# processor_main_connector.net
KiCad netlist of a schematic drawn in Altium Designer
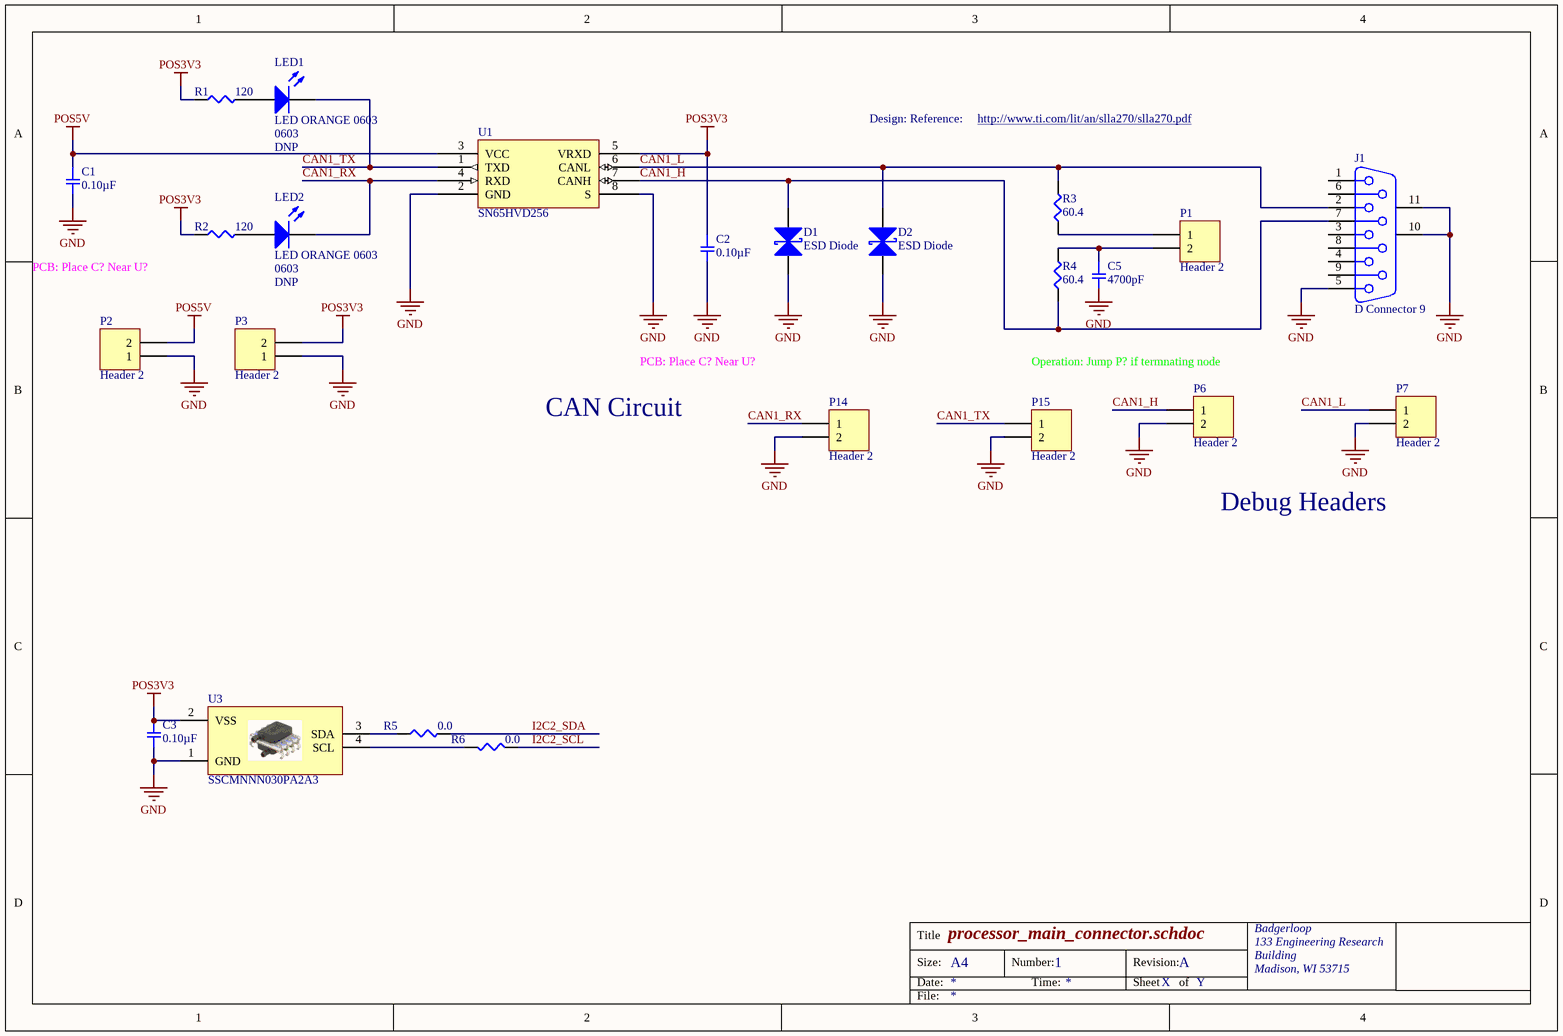
[diagram p0: processor_main_connector.SchDoc]

(export (version "E")
  (design (tool "Eeschema 10.0.6"))
  (components
    (comp (ref "C1")
      (value "0.10µF")
      (footprint "SMD-0805C")
      (description "CAP CER 0.1UF 50V X7R 0805")
      (fields
        (field (name "DIGI-KEY PART NUMBER") "490-11955-1-ND")
        (field (name "PART NUMBER") "GCD21BR71H104KA01L")
      )
      (libsource (lib "capacitor") (part "GCD21BR71H104KA01L"))
    )
    (comp (ref "C2")
      (value "0.10µF")
      (footprint "SMD-0805C")
      (description "CAP CER 0.1UF 50V X7R 0805")
      (fields
        (field (name "DIGI-KEY PART NUMBER") "490-11955-1-ND")
        (field (name "PART NUMBER") "GCD21BR71H104KA01L")
      )
      (libsource (lib "capacitor") (part "GCD21BR71H104KA01L"))
    )
    (comp (ref "C3")
      (value "0.10µF")
      (footprint "SMD-0805C")
      (description "CAP CER 0.1UF 50V X7R 0805")
      (fields
        (field (name "DIGI-KEY PART NUMBER") "490-11955-1-ND")
        (field (name "PART NUMBER") "GCD21BR71H104KA01L")
      )
      (libsource (lib "capacitor") (part "GCD21BR71H104KA01L"))
    )
    (comp (ref "C5")
      (value "4700pF")
      (footprint "SMD-0805C")
      (description "CAP CER 4700PF 50V NP0 0805")
      (fields
        (field (name "DIGI-KEY PART NUMBER") "490-4973-1-ND")
        (field (name "PART NUMBER") "GCM2165C1H472JA16D")
      )
      (libsource (lib "capacitor") (part "GCM2165C1H472JA16D"))
    )
    (comp (ref "D1")
      (value "ESD Diode")
      (footprint "SMD-0402-RES")
      (description "ESD Supressor")
      (fields (field (name "MANUFACTURER") "EZAEG"))
      (libsource (lib "temp") (part "ESD Diode"))
    )
    (comp (ref "D2")
      (value "ESD Diode")
      (footprint "SMD-0402-RES")
      (description "ESD Supressor")
      (fields (field (name "MANUFACTURER") "EZAEG"))
      (libsource (lib "temp") (part "ESD Diode"))
    )
    (comp (ref "J1")
      (value "D Connector 9")
      (footprint "DSUB1.385-2H9")
      (description "Receptacle Assembly, 9 Position, Right Angle")
      (fields (field (name "PUBLISHER") "Altium Limited"))
      (libsource (lib "connector") (part "D Connector 9"))
    )
    (comp (ref "LED1")
      (value "LED ORANGE 0603")
      (footprint "LED 0603 ORANGE")
      (description "A-0603UOC")
      (fields
        (field (name "MANUFACTURER") "Lighthouse LEDs")
        (field (name "PACKAGE / CASE") "0603")
        (field (name "DNP") "DNP")
      )
      (libsource (lib "misc") (part "LED ORANGE 0603"))
    )
    (comp (ref "LED2")
      (value "LED ORANGE 0603")
      (footprint "LED 0603 ORANGE")
      (description "A-0603UOC")
      (fields
        (field (name "MANUFACTURER") "Lighthouse LEDs")
        (field (name "PACKAGE / CASE") "0603")
        (field (name "DNP") "DNP")
      )
      (libsource (lib "misc") (part "LED ORANGE 0603"))
    )
    (comp (ref "P1")
      (value "Header 2")
      (footprint "Pin Header 1x2 TH Pitch 2.54mm")
      (description "Header, 2-Pin")
      (fields (field (name "PUBLISHER") "Altium Limited"))
      (libsource (lib "") (part "Header 2_1"))
    )
    (comp (ref "P2")
      (value "Header 2")
      (footprint "Pin Header 1x2 TH Pitch 2.54mm")
      (description "Header, 2-Pin")
      (fields (field (name "PUBLISHER") "Altium Limited"))
      (libsource (lib "connector") (part "Header 2"))
    )
    (comp (ref "P3")
      (value "Header 2")
      (footprint "Pin Header 1x2 TH Pitch 2.54mm")
      (description "Header, 2-Pin")
      (fields (field (name "PUBLISHER") "Altium Limited"))
      (libsource (lib "connector") (part "Header 2"))
    )
    (comp (ref "P6")
      (value "Header 2")
      (footprint "Pin Header 1x2 TH Pitch 2.54mm")
      (description "Header, 2-Pin")
      (fields (field (name "PUBLISHER") "Altium Limited"))
      (libsource (lib "") (part "Header 2_1"))
    )
    (comp (ref "P7")
      (value "Header 2")
      (footprint "Pin Header 1x2 TH Pitch 2.54mm")
      (description "Header, 2-Pin")
      (fields (field (name "PUBLISHER") "Altium Limited"))
      (libsource (lib "") (part "Header 2_1"))
    )
    (comp (ref "P14")
      (value "Header 2")
      (footprint "Pin Header 1x2 TH Pitch 2.54mm")
      (description "Header, 2-Pin")
      (fields (field (name "PUBLISHER") "Altium Limited"))
      (libsource (lib "") (part "Header 2_1"))
    )
    (comp (ref "P15")
      (value "Header 2")
      (footprint "Pin Header 1x2 TH Pitch 2.54mm")
      (description "Header, 2-Pin")
      (fields (field (name "PUBLISHER") "Altium Limited"))
      (libsource (lib "") (part "Header 2_1"))
    )
    (comp (ref "R1")
      (value "120")
      (footprint "SMD-0402-RES")
      (description "RES SMD 120 OHM 5% 1/10W 0402")
      (fields (field (name "PART NUMBER") "ERJ-2GEJ121X") (field (name "DIGI-KEY PART NUMBER") "P120JCT-ND"))
      (libsource (lib "resistor") (part "ERJ-2GEJ121X"))
    )
    (comp (ref "R2")
      (value "120")
      (footprint "SMD-0402-RES")
      (description "RES SMD 120 OHM 5% 1/10W 0402")
      (fields (field (name "PART NUMBER") "ERJ-2GEJ121X") (field (name "DIGI-KEY PART NUMBER") "P120JCT-ND"))
      (libsource (lib "resistor") (part "ERJ-2GEJ121X"))
    )
    (comp (ref "R3")
      (value "60.4")
      (footprint "SMD-0402-RES")
      (description "RES SMD 60.4 OHM 1% 1/10W 0402")
      (fields
        (field (name "PART NUMBER") "ERJ-2RKF60R4X")
        (field (name "DIGI-KEY PART NUMBER") "P60.4LCT-ND")
      )
      (libsource (lib "resistor") (part "ERJ-2RKF60R4X"))
    )
    (comp (ref "R4")
      (value "60.4")
      (footprint "SMD-0402-RES")
      (description "RES SMD 60.4 OHM 1% 1/10W 0402")
      (fields
        (field (name "PART NUMBER") "ERJ-2RKF60R4X")
        (field (name "DIGI-KEY PART NUMBER") "P60.4LCT-ND")
      )
      (libsource (lib "resistor") (part "ERJ-2RKF60R4X"))
    )
    (comp (ref "R5")
      (value "0.0")
      (footprint "SMD-0402-RES")
      (description "RES SMD 0.0OHM JUMPER 1/10W 0402")
      (fields (field (name "PART NUMBER") "ERJ-2GE0R00X") (field (name "DIGI-KEY PART NUMBER") "P0.0JCT-ND"))
      (libsource (lib "resistor") (part "ERJ-2GE0R00X"))
    )
    (comp (ref "R6")
      (value "0.0")
      (footprint "SMD-0402-RES")
      (description "RES SMD 0.0OHM JUMPER 1/10W 0402")
      (fields (field (name "PART NUMBER") "ERJ-2GE0R00X") (field (name "DIGI-KEY PART NUMBER") "P0.0JCT-ND"))
      (libsource (lib "resistor") (part "ERJ-2GE0R00X"))
    )
    (comp (ref "U1")
      (value "SN65HVD256")
      (footprint "SOIC127P630X175-8N")
      (description "IC TXRX CAN 5V HS 8SOIC")
      (fields (field (name "MANUFACTURER") "TI"))
      (libsource (lib "temp") (part "SN65HVD256"))
    )
    (comp (ref "U3")
      (value "SSCMNNN030PA2A3")
      (footprint "8-SMT")
      (description "Honeywell Digital Pressure Sensor")
      (libsource (lib "ic") (part "SSCMNNN030PA2A3"))
    )
  )
  (nets
    (net (code "1") (name "/CAN1_H") (class "Default")
      (node (ref "D1") (pin "2") (pinfunction "K_2") (pintype "passive"))
      (node (ref "J1") (pin "7") (pinfunction "7_7") (pintype "passive"))
      (node (ref "P6") (pin "1") (pinfunction "1_1") (pintype "passive"))
      (node (ref "R4") (pin "1") (pinfunction "1_1") (pintype "passive"))
      (node (ref "U1") (pin "7") (pinfunction "CANH_7") (pintype "bidirectional"))
    )
    (net (code "2") (name "/CAN1_L") (class "Default")
      (node (ref "D2") (pin "2") (pinfunction "K_2") (pintype "passive"))
      (node (ref "J1") (pin "2") (pinfunction "2_2") (pintype "passive"))
      (node (ref "P7") (pin "1") (pinfunction "1_1") (pintype "passive"))
      (node (ref "R3") (pin "2") (pinfunction "2_2") (pintype "passive"))
      (node (ref "U1") (pin "6") (pinfunction "CANL_6") (pintype "bidirectional"))
    )
    (net (code "3") (name "/CAN1_RX") (class "Default")
      (node (ref "LED2") (pin "2") (pinfunction "K_2") (pintype "passive"))
      (node (ref "P14") (pin "1") (pinfunction "1_1") (pintype "passive"))
      (node (ref "U1") (pin "4") (pinfunction "RXD_4") (pintype "input"))
    )
    (net (code "4") (name "/CAN1_TX") (class "Default")
      (node (ref "LED1") (pin "2") (pinfunction "K_2") (pintype "passive"))
      (node (ref "P15") (pin "1") (pinfunction "1_1") (pintype "passive"))
      (node (ref "U1") (pin "1") (pinfunction "TXD_1") (pintype "output"))
    )
    (net (code "5") (name "/I2C2_SCL") (class "Default")
      (node (ref "R6") (pin "1") (pinfunction "1_1") (pintype "passive"))
    )
    (net (code "6") (name "/I2C2_SDA") (class "Default")
      (node (ref "R5") (pin "2") (pinfunction "2_2") (pintype "passive"))
    )
    (net (code "7") (name "GND") (class "Default")
      (node (ref "C1") (pin "2") (pinfunction "2_2") (pintype "passive"))
      (node (ref "C2") (pin "2") (pinfunction "2_2") (pintype "passive"))
      (node (ref "C3") (pin "2") (pinfunction "2_2") (pintype "passive"))
      (node (ref "C5") (pin "2") (pinfunction "2_2") (pintype "passive"))
      (node (ref "D1") (pin "1") (pinfunction "A_1") (pintype "passive"))
      (node (ref "D2") (pin "1") (pinfunction "A_1") (pintype "passive"))
      (node (ref "J1") (pin "10") (pinfunction "MH1_10") (pintype "passive"))
      (node (ref "J1") (pin "11") (pinfunction "MH2_11") (pintype "passive"))
      (node (ref "J1") (pin "5") (pinfunction "5_5") (pintype "passive"))
      (node (ref "P14") (pin "2") (pinfunction "2_2") (pintype "passive"))
      (node (ref "P15") (pin "2") (pinfunction "2_2") (pintype "passive"))
      (node (ref "P2") (pin "1") (pinfunction "1_1") (pintype "passive"))
      (node (ref "P3") (pin "1") (pinfunction "1_1") (pintype "passive"))
      (node (ref "P6") (pin "2") (pinfunction "2_2") (pintype "passive"))
      (node (ref "P7") (pin "2") (pinfunction "2_2") (pintype "passive"))
      (node (ref "U1") (pin "2") (pinfunction "GND_2") (pintype "power_in"))
      (node (ref "U1") (pin "8") (pinfunction "S_8") (pintype "passive"))
      (node (ref "U3") (pin "1") (pinfunction "GND_1") (pintype "power_in"))
    )
    (net (code "8") (name "Net-(C5-Pad1)") (class "Default")
      (node (ref "C5") (pin "1") (pinfunction "1_1") (pintype "passive"))
      (node (ref "P1") (pin "2") (pinfunction "2_2") (pintype "passive"))
      (node (ref "R4") (pin "2") (pinfunction "2_2") (pintype "passive"))
    )
    (net (code "9") (name "Net-(LED1-A)") (class "Default")
      (node (ref "LED1") (pin "1") (pinfunction "A_1") (pintype "passive"))
      (node (ref "R1") (pin "2") (pinfunction "2_2") (pintype "passive"))
    )
    (net (code "10") (name "Net-(LED2-A)") (class "Default")
      (node (ref "LED2") (pin "1") (pinfunction "A_1") (pintype "passive"))
      (node (ref "R2") (pin "2") (pinfunction "2_2") (pintype "passive"))
    )
    (net (code "11") (name "Net-(P1-Pad1)") (class "Default")
      (node (ref "P1") (pin "1") (pinfunction "1_1") (pintype "passive"))
      (node (ref "R3") (pin "1") (pinfunction "1_1") (pintype "passive"))
    )
    (net (code "12") (name "Net-(U3-SCL)") (class "Default")
      (node (ref "R6") (pin "2") (pinfunction "2_2") (pintype "passive"))
      (node (ref "U3") (pin "4") (pinfunction "SCL_4") (pintype "passive"))
    )
    (net (code "13") (name "Net-(U3-SDA)") (class "Default")
      (node (ref "R5") (pin "1") (pinfunction "1_1") (pintype "passive"))
      (node (ref "U3") (pin "3") (pinfunction "SDA_3") (pintype "passive"))
    )
    (net (code "14") (name "POS3V3") (class "Default")
      (node (ref "C2") (pin "1") (pinfunction "1_1") (pintype "passive"))
      (node (ref "C3") (pin "1") (pinfunction "1_1") (pintype "passive"))
      (node (ref "P3") (pin "2") (pinfunction "2_2") (pintype "passive"))
      (node (ref "R1") (pin "1") (pinfunction "1_1") (pintype "passive"))
      (node (ref "R2") (pin "1") (pinfunction "1_1") (pintype "passive"))
      (node (ref "U1") (pin "5") (pinfunction "VRXD_5") (pintype "power_in"))
      (node (ref "U3") (pin "2") (pinfunction "VSS_2") (pintype "power_in"))
    )
    (net (code "15") (name "POS5V") (class "Default")
      (node (ref "C1") (pin "1") (pinfunction "1_1") (pintype "passive"))
      (node (ref "P2") (pin "2") (pinfunction "2_2") (pintype "passive"))
      (node (ref "U1") (pin "3") (pinfunction "VCC_3") (pintype "power_in"))
    )
    (net (code "16") (name "unconnected-(J1-Pad1)") (class "Default")
      (node (ref "J1") (pin "1") (pinfunction "1_1") (pintype "passive"))
    )
    (net (code "17") (name "unconnected-(J1-Pad3)") (class "Default")
      (node (ref "J1") (pin "3") (pinfunction "3_3") (pintype "passive"))
    )
    (net (code "18") (name "unconnected-(J1-Pad4)") (class "Default")
      (node (ref "J1") (pin "4") (pinfunction "4_4") (pintype "passive"))
    )
    (net (code "19") (name "unconnected-(J1-Pad6)") (class "Default")
      (node (ref "J1") (pin "6") (pinfunction "6_6") (pintype "passive"))
    )
    (net (code "20") (name "unconnected-(J1-Pad8)") (class "Default")
      (node (ref "J1") (pin "8") (pinfunction "8_8") (pintype "passive"))
    )
    (net (code "21") (name "unconnected-(J1-Pad9)") (class "Default")
      (node (ref "J1") (pin "9") (pinfunction "9_9") (pintype "passive"))
    )
  )
)
